# acdr.net
KiCad netlist of a schematic drawn in EAGLE
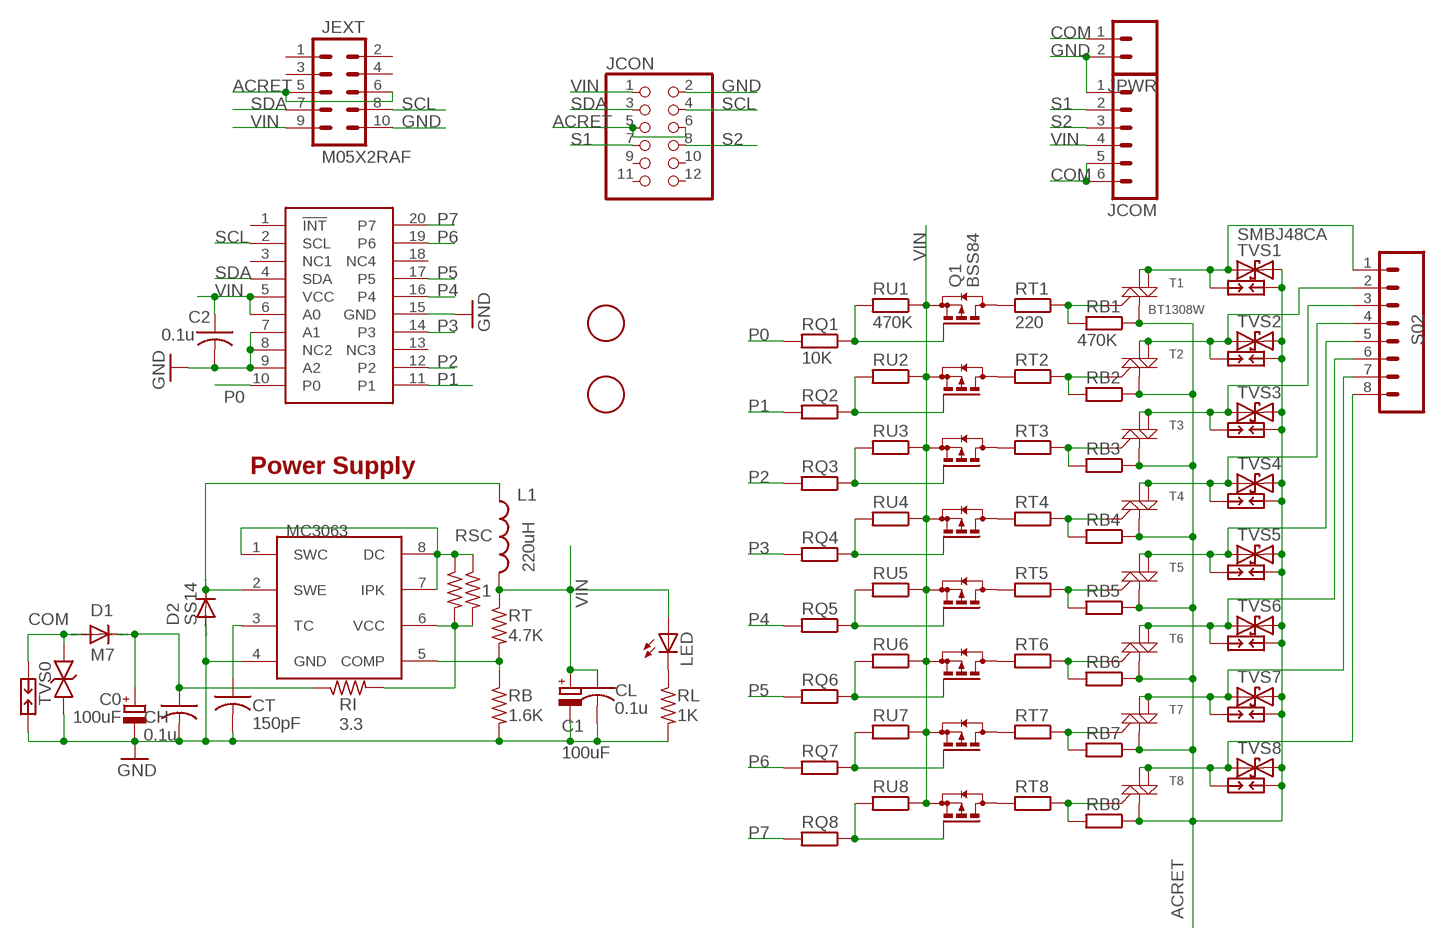
[diagram p0: schematic, sheet 1]

(export (version "E")
  (design (tool "Eeschema 10.0.6"))
  (components
    (comp (ref "C0")
      (value "100uF")
      (footprint "eagle-import:PANASONIC_E")
      (libsource (lib "eagle-import") (part "CPOL-EUE"))
    )
    (comp (ref "C1")
      (value "100uF")
      (footprint "eagle-import:PANASONIC_D")
      (libsource (lib "eagle-import") (part "CPOL-EUD"))
    )
    (comp (ref "C2")
      (value "0.1u")
      (footprint "eagle-import:C0603")
      (libsource (lib "eagle-import") (part "C-USC0603"))
    )
    (comp (ref "CH")
      (value "0.1u")
      (footprint "eagle-import:C0603")
      (libsource (lib "eagle-import") (part "C-USC0603"))
    )
    (comp (ref "CL")
      (value "0.1u")
      (footprint "eagle-import:C0603")
      (libsource (lib "eagle-import") (part "C-USC0603"))
    )
    (comp (ref "CT")
      (value "150pF")
      (footprint "eagle-import:C0603K")
      (libsource (lib "eagle-import") (part "C-USC0603K"))
    )
    (comp (ref "D1")
      (value "M7")
      (footprint "eagle-import:DO-214AC")
      (libsource (lib "eagle-import") (part "DIODE-DO-214AC"))
    )
    (comp (ref "D2")
      (value "SS14")
      (footprint "eagle-import:DO-214AC")
      (libsource (lib "eagle-import") (part "DIODE-DO-214AC"))
    )
    (comp (ref "JCOM")
      (value "M065MM")
      (footprint "eagle-import:SCREWTERMINAL-5MM-6")
      (libsource (lib "eagle-import") (part "M065MM"))
    )
    (comp (ref "JCON")
      (value "PINHD-2X6")
      (footprint "eagle-import:2X06")
      (libsource (lib "eagle-import") (part "PINHD-2X6"))
    )
    (comp (ref "JEXT")
      (value "M05X2RAF")
      (footprint "eagle-import:2X5-RAF")
      (libsource (lib "eagle-import") (part "M05X2RAF"))
    )
    (comp (ref "JPWR")
      (value "M024MM-X")
      (footprint "eagle-import:SCREWTERMINAL-4MM-2-X")
      (libsource (lib "eagle-import") (part "M024MM-X"))
    )
    (comp (ref "L1")
      (value "220uH")
      (footprint "eagle-import:SRU1038")
      (libsource (lib "eagle-import") (part "INDUCTORSRU1038"))
    )
    (comp (ref "LED")
      (value "LEDCHIPLED_0805")
      (footprint "eagle-import:CHIPLED_0805")
      (libsource (lib "eagle-import") (part "LEDCHIPLED_0805"))
    )
    (comp (ref "MC3063")
      (value "34063")
      (footprint "eagle-import:SO08")
      (libsource (lib "eagle-import") (part "MC33063/MC34063D"))
    )
    (comp (ref "PCF8574")
      (value "PCF8574")
      (footprint "eagle-import:SSOP20")
      (libsource (lib "eagle-import") (part "PCF8574"))
    )
    (comp (ref "Q1")
      (value "BSS84")
      (footprint "eagle-import:SOT23")
      (libsource (lib "eagle-import") (part "BSS84"))
    )
    (comp (ref "Q2")
      (value "BSS84")
      (footprint "eagle-import:SOT23")
      (libsource (lib "eagle-import") (part "BSS84"))
    )
    (comp (ref "Q3")
      (value "BSS84")
      (footprint "eagle-import:SOT23")
      (libsource (lib "eagle-import") (part "BSS84"))
    )
    (comp (ref "Q4")
      (value "BSS84")
      (footprint "eagle-import:SOT23")
      (libsource (lib "eagle-import") (part "BSS84"))
    )
    (comp (ref "Q5")
      (value "BSS84")
      (footprint "eagle-import:SOT23")
      (libsource (lib "eagle-import") (part "BSS84"))
    )
    (comp (ref "Q6")
      (value "BSS84")
      (footprint "eagle-import:SOT23")
      (libsource (lib "eagle-import") (part "BSS84"))
    )
    (comp (ref "Q7")
      (value "BSS84")
      (footprint "eagle-import:SOT23")
      (libsource (lib "eagle-import") (part "BSS84"))
    )
    (comp (ref "Q8")
      (value "BSS84")
      (footprint "eagle-import:SOT23")
      (libsource (lib "eagle-import") (part "BSS84"))
    )
    (comp (ref "RB")
      (value "1.6K")
      (footprint "eagle-import:R0603")
      (libsource (lib "eagle-import") (part "adafruitGood_R-US_R0603"))
    )
    (comp (ref "RB1")
      (value "470K")
      (footprint "eagle-import:R0603")
      (libsource (lib "eagle-import") (part "R-EU_R0603"))
    )
    (comp (ref "RB2")
      (value "470K")
      (footprint "eagle-import:R0603")
      (libsource (lib "eagle-import") (part "R-EU_R0603"))
    )
    (comp (ref "RB3")
      (value "470K")
      (footprint "eagle-import:R0603")
      (libsource (lib "eagle-import") (part "R-EU_R0603"))
    )
    (comp (ref "RB4")
      (value "470K")
      (footprint "eagle-import:R0603")
      (libsource (lib "eagle-import") (part "R-EU_R0603"))
    )
    (comp (ref "RB5")
      (value "470K")
      (footprint "eagle-import:R0603")
      (libsource (lib "eagle-import") (part "R-EU_R0603"))
    )
    (comp (ref "RB6")
      (value "470K")
      (footprint "eagle-import:R0603")
      (libsource (lib "eagle-import") (part "R-EU_R0603"))
    )
    (comp (ref "RB7")
      (value "470K")
      (footprint "eagle-import:R0603")
      (libsource (lib "eagle-import") (part "R-EU_R0603"))
    )
    (comp (ref "RB8")
      (value "470K")
      (footprint "eagle-import:R0603")
      (libsource (lib "eagle-import") (part "R-EU_R0603"))
    )
    (comp (ref "RI")
      (value "3.3")
      (footprint "eagle-import:R2010")
      (libsource (lib "eagle-import") (part "adafruitGood_R-US_R2010"))
    )
    (comp (ref "RL")
      (value "1K")
      (footprint "eagle-import:R0603")
      (libsource (lib "eagle-import") (part "R-US_R0603"))
    )
    (comp (ref "RQ1")
      (value "10K")
      (footprint "eagle-import:R0603")
      (libsource (lib "eagle-import") (part "R-EU_R0603"))
    )
    (comp (ref "RQ2")
      (value "10K")
      (footprint "eagle-import:R0603")
      (libsource (lib "eagle-import") (part "R-EU_R0603"))
    )
    (comp (ref "RQ3")
      (value "10K")
      (footprint "eagle-import:R0603")
      (libsource (lib "eagle-import") (part "R-EU_R0603"))
    )
    (comp (ref "RQ4")
      (value "10K")
      (footprint "eagle-import:R0603")
      (libsource (lib "eagle-import") (part "R-EU_R0603"))
    )
    (comp (ref "RQ5")
      (value "10K")
      (footprint "eagle-import:R0603")
      (libsource (lib "eagle-import") (part "R-EU_R0603"))
    )
    (comp (ref "RQ6")
      (value "10K")
      (footprint "eagle-import:R0603")
      (libsource (lib "eagle-import") (part "R-EU_R0603"))
    )
    (comp (ref "RQ7")
      (value "10K")
      (footprint "eagle-import:R0603")
      (libsource (lib "eagle-import") (part "R-EU_R0603"))
    )
    (comp (ref "RQ8")
      (value "10K")
      (footprint "eagle-import:R0603")
      (libsource (lib "eagle-import") (part "R-EU_R0603"))
    )
    (comp (ref "RSC")
      (value "1")
      (footprint "eagle-import:R0805")
      (libsource (lib "eagle-import") (part "adafruitGood_R-US_R0805"))
    )
    (comp (ref "RSC1")
      (value "1")
      (footprint "eagle-import:R0805")
      (libsource (lib "eagle-import") (part "adafruitGood_R-US_R0805"))
    )
    (comp (ref "RT")
      (value "4.7K")
      (footprint "eagle-import:R0805")
      (libsource (lib "eagle-import") (part "adafruitGood_R-US_R0805"))
    )
    (comp (ref "RT1")
      (value "220")
      (footprint "eagle-import:R0603")
      (libsource (lib "eagle-import") (part "R-EU_R0603"))
    )
    (comp (ref "RT2")
      (value "220")
      (footprint "eagle-import:R0603")
      (libsource (lib "eagle-import") (part "R-EU_R0603"))
    )
    (comp (ref "RT3")
      (value "220")
      (footprint "eagle-import:R0603")
      (libsource (lib "eagle-import") (part "R-EU_R0603"))
    )
    (comp (ref "RT4")
      (value "220")
      (footprint "eagle-import:R0603")
      (libsource (lib "eagle-import") (part "R-EU_R0603"))
    )
    (comp (ref "RT5")
      (value "220")
      (footprint "eagle-import:R0603")
      (libsource (lib "eagle-import") (part "R-EU_R0603"))
    )
    (comp (ref "RT6")
      (value "220")
      (footprint "eagle-import:R0603")
      (libsource (lib "eagle-import") (part "R-EU_R0603"))
    )
    (comp (ref "RT7")
      (value "220")
      (footprint "eagle-import:R0603")
      (libsource (lib "eagle-import") (part "R-EU_R0603"))
    )
    (comp (ref "RT8")
      (value "220")
      (footprint "eagle-import:R0603")
      (libsource (lib "eagle-import") (part "R-EU_R0603"))
    )
    (comp (ref "RU1")
      (value "470K")
      (footprint "eagle-import:R0603")
      (libsource (lib "eagle-import") (part "R-EU_R0603"))
    )
    (comp (ref "RU2")
      (value "470K")
      (footprint "eagle-import:R0603")
      (libsource (lib "eagle-import") (part "R-EU_R0603"))
    )
    (comp (ref "RU3")
      (value "470K")
      (footprint "eagle-import:R0603")
      (libsource (lib "eagle-import") (part "R-EU_R0603"))
    )
    (comp (ref "RU4")
      (value "470K")
      (footprint "eagle-import:R0603")
      (libsource (lib "eagle-import") (part "R-EU_R0603"))
    )
    (comp (ref "RU5")
      (value "470K")
      (footprint "eagle-import:R0603")
      (libsource (lib "eagle-import") (part "R-EU_R0603"))
    )
    (comp (ref "RU6")
      (value "470K")
      (footprint "eagle-import:R0603")
      (libsource (lib "eagle-import") (part "R-EU_R0603"))
    )
    (comp (ref "RU7")
      (value "470K")
      (footprint "eagle-import:R0603")
      (libsource (lib "eagle-import") (part "R-EU_R0603"))
    )
    (comp (ref "RU8")
      (value "470K")
      (footprint "eagle-import:R0603")
      (libsource (lib "eagle-import") (part "R-EU_R0603"))
    )
    (comp (ref "S02")
      (value "M085MM-8")
      (footprint "eagle-import:SCREWTERMINAL-5MM-8")
      (libsource (lib "eagle-import") (part "M085MM-8"))
    )
    (comp (ref "SP0")
      (value "PCB-SGAP")
      (footprint "eagle-import:PCB-SGAP")
      (libsource (lib "eagle-import") (part "PCB-SGAP"))
    )
    (comp (ref "SP1")
      (value "PCB-SGAP")
      (footprint "eagle-import:PCB-SGAP")
      (libsource (lib "eagle-import") (part "PCB-SGAP"))
    )
    (comp (ref "SP2")
      (value "PCB-SGAP")
      (footprint "eagle-import:PCB-SGAP")
      (libsource (lib "eagle-import") (part "PCB-SGAP"))
    )
    (comp (ref "SP3")
      (value "PCB-SGAP")
      (footprint "eagle-import:PCB-SGAP")
      (libsource (lib "eagle-import") (part "PCB-SGAP"))
    )
    (comp (ref "SP4")
      (value "PCB-SGAP")
      (footprint "eagle-import:PCB-SGAP")
      (libsource (lib "eagle-import") (part "PCB-SGAP"))
    )
    (comp (ref "SP5")
      (value "PCB-SGAP")
      (footprint "eagle-import:PCB-SGAP")
      (libsource (lib "eagle-import") (part "PCB-SGAP"))
    )
    (comp (ref "SP6")
      (value "PCB-SGAP")
      (footprint "eagle-import:PCB-SGAP")
      (libsource (lib "eagle-import") (part "PCB-SGAP"))
    )
    (comp (ref "SP7")
      (value "PCB-SGAP")
      (footprint "eagle-import:PCB-SGAP")
      (libsource (lib "eagle-import") (part "PCB-SGAP"))
    )
    (comp (ref "SP8")
      (value "PCB-SGAP")
      (footprint "eagle-import:PCB-SGAP")
      (libsource (lib "eagle-import") (part "PCB-SGAP"))
    )
    (comp (ref "T1")
      (value "BT1308W")
      (footprint "eagle-import:SOT223")
      (libsource (lib "eagle-import") (part "MAC97SOT223"))
    )
    (comp (ref "T2")
      (value "MAC97SOT223")
      (footprint "eagle-import:SOT223")
      (libsource (lib "eagle-import") (part "MAC97SOT223"))
    )
    (comp (ref "T3")
      (value "MAC97SOT223")
      (footprint "eagle-import:SOT223")
      (libsource (lib "eagle-import") (part "MAC97SOT223"))
    )
    (comp (ref "T4")
      (value "MAC97SOT223")
      (footprint "eagle-import:SOT223")
      (libsource (lib "eagle-import") (part "MAC97SOT223"))
    )
    (comp (ref "T5")
      (value "MAC97SOT223")
      (footprint "eagle-import:SOT223")
      (libsource (lib "eagle-import") (part "MAC97SOT223"))
    )
    (comp (ref "T6")
      (value "MAC97SOT223")
      (footprint "eagle-import:SOT223")
      (libsource (lib "eagle-import") (part "MAC97SOT223"))
    )
    (comp (ref "T7")
      (value "MAC97SOT223")
      (footprint "eagle-import:SOT223")
      (libsource (lib "eagle-import") (part "MAC97SOT223"))
    )
    (comp (ref "T8")
      (value "MAC97SOT223")
      (footprint "eagle-import:SOT223")
      (libsource (lib "eagle-import") (part "MAC97SOT223"))
    )
    (comp (ref "TVS0")
      (value "43CA")
      (footprint "eagle-import:SMB")
      (libsource (lib "eagle-import") (part "DIODE-BTVSSMB"))
    )
    (comp (ref "TVS1")
      (value "SMBJ48CA")
      (footprint "eagle-import:SMB")
      (libsource (lib "eagle-import") (part "TVSSMB"))
    )
    (comp (ref "TVS2")
      (value "TVSSMB")
      (footprint "eagle-import:SMB")
      (libsource (lib "eagle-import") (part "TVSSMB"))
    )
    (comp (ref "TVS3")
      (value "TVSSMB")
      (footprint "eagle-import:SMB")
      (libsource (lib "eagle-import") (part "TVSSMB"))
    )
    (comp (ref "TVS4")
      (value "TVSSMB")
      (footprint "eagle-import:SMB")
      (libsource (lib "eagle-import") (part "TVSSMB"))
    )
    (comp (ref "TVS5")
      (value "TVSSMB")
      (footprint "eagle-import:SMB")
      (libsource (lib "eagle-import") (part "TVSSMB"))
    )
    (comp (ref "TVS6")
      (value "TVSSMB")
      (footprint "eagle-import:SMB")
      (libsource (lib "eagle-import") (part "TVSSMB"))
    )
    (comp (ref "TVS7")
      (value "TVSSMB")
      (footprint "eagle-import:SMB")
      (libsource (lib "eagle-import") (part "TVSSMB"))
    )
    (comp (ref "TVS8")
      (value "TVSSMB")
      (footprint "eagle-import:SMB")
      (libsource (lib "eagle-import") (part "TVSSMB"))
    )
    (comp (ref "U$1")
      (value "FIDUCIAL")
      (footprint "eagle-import:FIDUCIAL_1MM")
      (libsource (lib "eagle-import") (part "FIDUCIAL"))
    )
    (comp (ref "U$2")
      (value "FIDUCIAL")
      (footprint "eagle-import:FIDUCIAL_1MM")
      (libsource (lib "eagle-import") (part "FIDUCIAL"))
    )
  )
  (nets
    (net (code "1") (name "/ACRET") (class "Default")
      (node (ref "JCON") (pin "5") (pinfunction "5_5") (pintype "passive"))
      (node (ref "JCON") (pin "6") (pinfunction "6_6") (pintype "passive"))
      (node (ref "JEXT") (pin "5") (pinfunction "5_5") (pintype "passive"))
      (node (ref "JEXT") (pin "6") (pinfunction "6_6") (pintype "passive"))
      (node (ref "RB1") (pin "1") (pinfunction "1_1") (pintype "passive"))
      (node (ref "RB2") (pin "1") (pinfunction "1_1") (pintype "passive"))
      (node (ref "RB3") (pin "1") (pinfunction "1_1") (pintype "passive"))
      (node (ref "RB4") (pin "1") (pinfunction "1_1") (pintype "passive"))
      (node (ref "RB5") (pin "1") (pinfunction "1_1") (pintype "passive"))
      (node (ref "RB6") (pin "1") (pinfunction "1_1") (pintype "passive"))
      (node (ref "RB7") (pin "1") (pinfunction "1_1") (pintype "passive"))
      (node (ref "RB8") (pin "1") (pinfunction "1_1") (pintype "passive"))
      (node (ref "SP1") (pin "1") (pinfunction "1_1") (pintype "passive"))
      (node (ref "SP2") (pin "1") (pinfunction "1_1") (pintype "passive"))
      (node (ref "SP3") (pin "1") (pinfunction "1_1") (pintype "passive"))
      (node (ref "SP4") (pin "1") (pinfunction "1_1") (pintype "passive"))
      (node (ref "SP5") (pin "1") (pinfunction "1_1") (pintype "passive"))
      (node (ref "SP6") (pin "1") (pinfunction "1_1") (pintype "passive"))
      (node (ref "SP7") (pin "1") (pinfunction "1_1") (pintype "passive"))
      (node (ref "SP8") (pin "1") (pinfunction "1_1") (pintype "passive"))
      (node (ref "T1") (pin "1") (pinfunction "M1_1") (pintype "bidirectional"))
      (node (ref "T2") (pin "1") (pinfunction "M1_1") (pintype "bidirectional"))
      (node (ref "T3") (pin "1") (pinfunction "M1_1") (pintype "bidirectional"))
      (node (ref "T4") (pin "1") (pinfunction "M1_1") (pintype "bidirectional"))
      (node (ref "T5") (pin "1") (pinfunction "M1_1") (pintype "bidirectional"))
      (node (ref "T6") (pin "1") (pinfunction "M1_1") (pintype "bidirectional"))
      (node (ref "T7") (pin "1") (pinfunction "M1_1") (pintype "bidirectional"))
      (node (ref "T8") (pin "1") (pinfunction "M1_1") (pintype "bidirectional"))
      (node (ref "TVS1") (pin "C") (pinfunction "C_C") (pintype "passive"))
      (node (ref "TVS2") (pin "C") (pinfunction "C_C") (pintype "passive"))
      (node (ref "TVS3") (pin "C") (pinfunction "C_C") (pintype "passive"))
      (node (ref "TVS4") (pin "C") (pinfunction "C_C") (pintype "passive"))
      (node (ref "TVS5") (pin "C") (pinfunction "C_C") (pintype "passive"))
      (node (ref "TVS6") (pin "C") (pinfunction "C_C") (pintype "passive"))
      (node (ref "TVS7") (pin "C") (pinfunction "C_C") (pintype "passive"))
      (node (ref "TVS8") (pin "C") (pinfunction "C_C") (pintype "passive"))
    )
    (net (code "2") (name "/COM") (class "Default")
      (node (ref "D1") (pin "A") (pinfunction "A_A") (pintype "passive"))
      (node (ref "JCOM") (pin "5") (pinfunction "5_5") (pintype "passive"))
      (node (ref "JCOM") (pin "6") (pinfunction "6_6") (pintype "passive"))
      (node (ref "JPWR") (pin "1") (pinfunction "1_1") (pintype "passive"))
      (node (ref "SP0") (pin "1") (pinfunction "1_1") (pintype "passive"))
      (node (ref "TVS0") (pin "C") (pinfunction "C_C") (pintype "passive"))
    )
    (net (code "3") (name "/P0") (class "Default")
      (node (ref "PCF8574") (pin "10") (pinfunction "P0_10") (pintype "bidirectional"))
      (node (ref "RQ1") (pin "2") (pinfunction "2_2") (pintype "passive"))
    )
    (net (code "4") (name "/P1") (class "Default")
      (node (ref "PCF8574") (pin "11") (pinfunction "P1_11") (pintype "bidirectional"))
      (node (ref "RQ2") (pin "2") (pinfunction "2_2") (pintype "passive"))
    )
    (net (code "5") (name "/P2") (class "Default")
      (node (ref "PCF8574") (pin "12") (pinfunction "P2_12") (pintype "bidirectional"))
      (node (ref "RQ3") (pin "2") (pinfunction "2_2") (pintype "passive"))
    )
    (net (code "6") (name "/P3") (class "Default")
      (node (ref "PCF8574") (pin "14") (pinfunction "P3_14") (pintype "bidirectional"))
      (node (ref "RQ4") (pin "2") (pinfunction "2_2") (pintype "passive"))
    )
    (net (code "7") (name "/P4") (class "Default")
      (node (ref "PCF8574") (pin "16") (pinfunction "P4_16") (pintype "bidirectional"))
      (node (ref "RQ5") (pin "2") (pinfunction "2_2") (pintype "passive"))
    )
    (net (code "8") (name "/P5") (class "Default")
      (node (ref "PCF8574") (pin "17") (pinfunction "P5_17") (pintype "bidirectional"))
      (node (ref "RQ6") (pin "2") (pinfunction "2_2") (pintype "passive"))
    )
    (net (code "9") (name "/P6") (class "Default")
      (node (ref "PCF8574") (pin "19") (pinfunction "P6_19") (pintype "bidirectional"))
      (node (ref "RQ7") (pin "2") (pinfunction "2_2") (pintype "passive"))
    )
    (net (code "10") (name "/P7") (class "Default")
      (node (ref "PCF8574") (pin "20") (pinfunction "P7_20") (pintype "bidirectional"))
      (node (ref "RQ8") (pin "2") (pinfunction "2_2") (pintype "passive"))
    )
    (net (code "11") (name "/S1") (class "Default")
      (node (ref "JCOM") (pin "2") (pinfunction "2_2") (pintype "passive"))
      (node (ref "JCON") (pin "7") (pinfunction "7_7") (pintype "passive"))
    )
    (net (code "12") (name "/S2") (class "Default")
      (node (ref "JCOM") (pin "3") (pinfunction "3_3") (pintype "passive"))
      (node (ref "JCON") (pin "8") (pinfunction "8_8") (pintype "passive"))
    )
    (net (code "13") (name "/SCL") (class "Default")
      (node (ref "JCON") (pin "4") (pinfunction "4_4") (pintype "passive"))
      (node (ref "JEXT") (pin "8") (pinfunction "8_8") (pintype "passive"))
      (node (ref "PCF8574") (pin "2") (pinfunction "SCL_2") (pintype "bidirectional"))
    )
    (net (code "14") (name "/SDA") (class "Default")
      (node (ref "JCON") (pin "3") (pinfunction "3_3") (pintype "passive"))
      (node (ref "JEXT") (pin "7") (pinfunction "7_7") (pintype "passive"))
      (node (ref "PCF8574") (pin "4") (pinfunction "SDA_4") (pintype "bidirectional"))
    )
    (net (code "15") (name "/VIN") (class "Default")
      (node (ref "C1") (pin "+") (pinfunction "+_+") (pintype "passive"))
      (node (ref "C2") (pin "1") (pinfunction "1_1") (pintype "passive"))
      (node (ref "CL") (pin "1") (pinfunction "1_1") (pintype "passive"))
      (node (ref "JCOM") (pin "4") (pinfunction "4_4") (pintype "passive"))
      (node (ref "JCON") (pin "1") (pinfunction "1_1") (pintype "passive"))
      (node (ref "JEXT") (pin "9") (pinfunction "9_9") (pintype "passive"))
      (node (ref "L1") (pin "2") (pinfunction "2_2") (pintype "passive"))
      (node (ref "LED") (pin "A") (pinfunction "A_A") (pintype "passive"))
      (node (ref "PCF8574") (pin "5") (pinfunction "VCC_5") (pintype "power_in"))
      (node (ref "PCF8574") (pin "6") (pinfunction "A0_6") (pintype "bidirectional"))
      (node (ref "Q1") (pin "2") (pinfunction "S_2") (pintype "passive"))
      (node (ref "Q2") (pin "2") (pinfunction "S_2") (pintype "passive"))
      (node (ref "Q3") (pin "2") (pinfunction "S_2") (pintype "passive"))
      (node (ref "Q4") (pin "2") (pinfunction "S_2") (pintype "passive"))
      (node (ref "Q5") (pin "2") (pinfunction "S_2") (pintype "passive"))
      (node (ref "Q6") (pin "2") (pinfunction "S_2") (pintype "passive"))
      (node (ref "Q7") (pin "2") (pinfunction "S_2") (pintype "passive"))
      (node (ref "Q8") (pin "2") (pinfunction "S_2") (pintype "passive"))
      (node (ref "RT") (pin "1") (pinfunction "1_1") (pintype "passive"))
      (node (ref "RU1") (pin "1") (pinfunction "1_1") (pintype "passive"))
      (node (ref "RU2") (pin "1") (pinfunction "1_1") (pintype "passive"))
      (node (ref "RU3") (pin "1") (pinfunction "1_1") (pintype "passive"))
      (node (ref "RU4") (pin "1") (pinfunction "1_1") (pintype "passive"))
      (node (ref "RU5") (pin "1") (pinfunction "1_1") (pintype "passive"))
      (node (ref "RU6") (pin "1") (pinfunction "1_1") (pintype "passive"))
      (node (ref "RU7") (pin "1") (pinfunction "1_1") (pintype "passive"))
      (node (ref "RU8") (pin "1") (pinfunction "1_1") (pintype "passive"))
    )
    (net (code "16") (name "GND") (class "Default")
      (node (ref "C0") (pin "-") (pinfunction "-_-") (pintype "passive"))
      (node (ref "C1") (pin "-") (pinfunction "-_-") (pintype "passive"))
      (node (ref "C2") (pin "2") (pinfunction "2_2") (pintype "passive"))
      (node (ref "CH") (pin "2") (pinfunction "2_2") (pintype "passive"))
      (node (ref "CL") (pin "2") (pinfunction "2_2") (pintype "passive"))
      (node (ref "CT") (pin "2") (pinfunction "2_2") (pintype "passive"))
      (node (ref "D2") (pin "A") (pinfunction "A_A") (pintype "passive"))
      (node (ref "JCOM") (pin "1") (pinfunction "1_1") (pintype "passive"))
      (node (ref "JCON") (pin "2") (pinfunction "2_2") (pintype "passive"))
      (node (ref "JEXT") (pin "10") (pinfunction "10_10") (pintype "passive"))
      (node (ref "JPWR") (pin "2") (pinfunction "2_2") (pintype "passive"))
      (node (ref "MC3063") (pin "4") (pinfunction "GND_4") (pintype "power_in"))
      (node (ref "PCF8574") (pin "15") (pinfunction "GND_15") (pintype "power_in"))
      (node (ref "PCF8574") (pin "7") (pinfunction "A1_7") (pintype "bidirectional"))
      (node (ref "PCF8574") (pin "8") (pinfunction "NC2_8") (pintype "bidirectional"))
      (node (ref "PCF8574") (pin "9") (pinfunction "A2_9") (pintype "bidirectional"))
      (node (ref "RB") (pin "2") (pinfunction "2_2") (pintype "passive"))
      (node (ref "RL") (pin "2") (pinfunction "2_2") (pintype "passive"))
      (node (ref "SP0") (pin "2") (pinfunction "2_2") (pintype "passive"))
      (node (ref "TVS0") (pin "A") (pinfunction "A_A") (pintype "passive"))
    )
    (net (code "17") (name "Net-(C0-Pad+)") (class "Default")
      (node (ref "C0") (pin "+") (pinfunction "+_+") (pintype "passive"))
      (node (ref "CH") (pin "1") (pinfunction "1_1") (pintype "passive"))
      (node (ref "D1") (pin "C") (pinfunction "C_C") (pintype "passive"))
      (node (ref "RI") (pin "1") (pinfunction "1_1") (pintype "passive"))
    )
    (net (code "18") (name "Net-(LED-PadC)") (class "Default")
      (node (ref "LED") (pin "C") (pinfunction "C_C") (pintype "passive"))
      (node (ref "RL") (pin "1") (pinfunction "1_1") (pintype "passive"))
    )
    (net (code "19") (name "Net-(MC3063-COMP)") (class "Default")
      (node (ref "MC3063") (pin "5") (pinfunction "COMP_5") (pintype "input"))
      (node (ref "RB") (pin "1") (pinfunction "1_1") (pintype "passive"))
      (node (ref "RT") (pin "2") (pinfunction "2_2") (pintype "passive"))
    )
    (net (code "20") (name "Net-(MC3063-DC)") (class "Default")
      (node (ref "MC3063") (pin "1") (pinfunction "SWC_1") (pintype "input"))
      (node (ref "MC3063") (pin "7") (pinfunction "IPK_7") (pintype "bidirectional"))
      (node (ref "MC3063") (pin "8") (pinfunction "DC_8") (pintype "input"))
      (node (ref "RSC") (pin "1") (pinfunction "1_1") (pintype "passive"))
      (node (ref "RSC1") (pin "1") (pinfunction "1_1") (pintype "passive"))
    )
    (net (code "21") (name "Net-(MC3063-SWE)") (class "Default")
      (node (ref "D2") (pin "C") (pinfunction "C_C") (pintype "passive"))
      (node (ref "L1") (pin "1") (pinfunction "1_1") (pintype "passive"))
      (node (ref "MC3063") (pin "2") (pinfunction "SWE_2") (pintype "input"))
    )
    (net (code "22") (name "Net-(MC3063-TC)") (class "Default")
      (node (ref "CT") (pin "1") (pinfunction "1_1") (pintype "passive"))
      (node (ref "MC3063") (pin "3") (pinfunction "TC_3") (pintype "input"))
    )
    (net (code "23") (name "Net-(MC3063-VCC)") (class "Default")
      (node (ref "MC3063") (pin "6") (pinfunction "VCC_6") (pintype "power_in"))
      (node (ref "RI") (pin "2") (pinfunction "2_2") (pintype "passive"))
      (node (ref "RSC") (pin "2") (pinfunction "2_2") (pintype "passive"))
      (node (ref "RSC1") (pin "2") (pinfunction "2_2") (pintype "passive"))
    )
    (net (code "24") (name "Net-(Q1-D)") (class "Default")
      (node (ref "Q1") (pin "3") (pinfunction "D_3") (pintype "passive"))
      (node (ref "RT1") (pin "2") (pinfunction "2_2") (pintype "passive"))
    )
    (net (code "25") (name "Net-(Q1-G)") (class "Default")
      (node (ref "Q1") (pin "1") (pinfunction "G_1") (pintype "passive"))
      (node (ref "RQ1") (pin "1") (pinfunction "1_1") (pintype "passive"))
      (node (ref "RU1") (pin "2") (pinfunction "2_2") (pintype "passive"))
    )
    (net (code "26") (name "Net-(Q2-D)") (class "Default")
      (node (ref "Q2") (pin "3") (pinfunction "D_3") (pintype "passive"))
      (node (ref "RT2") (pin "2") (pinfunction "2_2") (pintype "passive"))
    )
    (net (code "27") (name "Net-(Q2-G)") (class "Default")
      (node (ref "Q2") (pin "1") (pinfunction "G_1") (pintype "passive"))
      (node (ref "RQ2") (pin "1") (pinfunction "1_1") (pintype "passive"))
      (node (ref "RU2") (pin "2") (pinfunction "2_2") (pintype "passive"))
    )
    (net (code "28") (name "Net-(Q3-D)") (class "Default")
      (node (ref "Q3") (pin "3") (pinfunction "D_3") (pintype "passive"))
      (node (ref "RT3") (pin "2") (pinfunction "2_2") (pintype "passive"))
    )
    (net (code "29") (name "Net-(Q3-G)") (class "Default")
      (node (ref "Q3") (pin "1") (pinfunction "G_1") (pintype "passive"))
      (node (ref "RQ3") (pin "1") (pinfunction "1_1") (pintype "passive"))
      (node (ref "RU3") (pin "2") (pinfunction "2_2") (pintype "passive"))
    )
    (net (code "30") (name "Net-(Q4-D)") (class "Default")
      (node (ref "Q4") (pin "3") (pinfunction "D_3") (pintype "passive"))
      (node (ref "RT4") (pin "2") (pinfunction "2_2") (pintype "passive"))
    )
    (net (code "31") (name "Net-(Q4-G)") (class "Default")
      (node (ref "Q4") (pin "1") (pinfunction "G_1") (pintype "passive"))
      (node (ref "RQ4") (pin "1") (pinfunction "1_1") (pintype "passive"))
      (node (ref "RU4") (pin "2") (pinfunction "2_2") (pintype "passive"))
    )
    (net (code "32") (name "Net-(Q5-D)") (class "Default")
      (node (ref "Q5") (pin "3") (pinfunction "D_3") (pintype "passive"))
      (node (ref "RT5") (pin "2") (pinfunction "2_2") (pintype "passive"))
    )
    (net (code "33") (name "Net-(Q5-G)") (class "Default")
      (node (ref "Q5") (pin "1") (pinfunction "G_1") (pintype "passive"))
      (node (ref "RQ5") (pin "1") (pinfunction "1_1") (pintype "passive"))
      (node (ref "RU5") (pin "2") (pinfunction "2_2") (pintype "passive"))
    )
    (net (code "34") (name "Net-(Q6-D)") (class "Default")
      (node (ref "Q6") (pin "3") (pinfunction "D_3") (pintype "passive"))
      (node (ref "RT6") (pin "2") (pinfunction "2_2") (pintype "passive"))
    )
    (net (code "35") (name "Net-(Q6-G)") (class "Default")
      (node (ref "Q6") (pin "1") (pinfunction "G_1") (pintype "passive"))
      (node (ref "RQ6") (pin "1") (pinfunction "1_1") (pintype "passive"))
      (node (ref "RU6") (pin "2") (pinfunction "2_2") (pintype "passive"))
    )
    (net (code "36") (name "Net-(Q7-D)") (class "Default")
      (node (ref "Q7") (pin "3") (pinfunction "D_3") (pintype "passive"))
      (node (ref "RT7") (pin "2") (pinfunction "2_2") (pintype "passive"))
    )
    (net (code "37") (name "Net-(Q7-G)") (class "Default")
      (node (ref "Q7") (pin "1") (pinfunction "G_1") (pintype "passive"))
      (node (ref "RQ7") (pin "1") (pinfunction "1_1") (pintype "passive"))
      (node (ref "RU7") (pin "2") (pinfunction "2_2") (pintype "passive"))
    )
    (net (code "38") (name "Net-(Q8-D)") (class "Default")
      (node (ref "Q8") (pin "3") (pinfunction "D_3") (pintype "passive"))
      (node (ref "RT8") (pin "2") (pinfunction "2_2") (pintype "passive"))
    )
    (net (code "39") (name "Net-(Q8-G)") (class "Default")
      (node (ref "Q8") (pin "1") (pinfunction "G_1") (pintype "passive"))
      (node (ref "RQ8") (pin "1") (pinfunction "1_1") (pintype "passive"))
      (node (ref "RU8") (pin "2") (pinfunction "2_2") (pintype "passive"))
    )
    (net (code "40") (name "Net-(T1-G)") (class "Default")
      (node (ref "RB1") (pin "2") (pinfunction "2_2") (pintype "passive"))
      (node (ref "RT1") (pin "1") (pinfunction "1_1") (pintype "passive"))
      (node (ref "T1") (pin "3") (pinfunction "G_3") (pintype "bidirectional"))
    )
    (net (code "41") (name "Net-(T1-M2)") (class "Default")
      (node (ref "S02") (pin "1") (pinfunction "1_1") (pintype "passive"))
      (node (ref "SP1") (pin "2") (pinfunction "2_2") (pintype "passive"))
      (node (ref "T1") (pin "2") (pinfunction "M2_2") (pintype "bidirectional"))
      (node (ref "T1") (pin "4") (pinfunction "M2-4_4") (pintype "bidirectional"))
      (node (ref "TVS1") (pin "A") (pinfunction "A_A") (pintype "passive"))
    )
    (net (code "42") (name "Net-(T2-G)") (class "Default")
      (node (ref "RB2") (pin "2") (pinfunction "2_2") (pintype "passive"))
      (node (ref "RT2") (pin "1") (pinfunction "1_1") (pintype "passive"))
      (node (ref "T2") (pin "3") (pinfunction "G_3") (pintype "bidirectional"))
    )
    (net (code "43") (name "Net-(T2-M2)") (class "Default")
      (node (ref "S02") (pin "2") (pinfunction "2_2") (pintype "passive"))
      (node (ref "SP2") (pin "2") (pinfunction "2_2") (pintype "passive"))
      (node (ref "T2") (pin "2") (pinfunction "M2_2") (pintype "bidirectional"))
      (node (ref "T2") (pin "4") (pinfunction "M2-4_4") (pintype "bidirectional"))
      (node (ref "TVS2") (pin "A") (pinfunction "A_A") (pintype "passive"))
    )
    (net (code "44") (name "Net-(T3-G)") (class "Default")
      (node (ref "RB3") (pin "2") (pinfunction "2_2") (pintype "passive"))
      (node (ref "RT3") (pin "1") (pinfunction "1_1") (pintype "passive"))
      (node (ref "T3") (pin "3") (pinfunction "G_3") (pintype "bidirectional"))
    )
    (net (code "45") (name "Net-(T3-M2)") (class "Default")
      (node (ref "S02") (pin "3") (pinfunction "3_3") (pintype "passive"))
      (node (ref "SP3") (pin "2") (pinfunction "2_2") (pintype "passive"))
      (node (ref "T3") (pin "2") (pinfunction "M2_2") (pintype "bidirectional"))
      (node (ref "T3") (pin "4") (pinfunction "M2-4_4") (pintype "bidirectional"))
      (node (ref "TVS3") (pin "A") (pinfunction "A_A") (pintype "passive"))
    )
    (net (code "46") (name "Net-(T4-G)") (class "Default")
      (node (ref "RB4") (pin "2") (pinfunction "2_2") (pintype "passive"))
      (node (ref "RT4") (pin "1") (pinfunction "1_1") (pintype "passive"))
      (node (ref "T4") (pin "3") (pinfunction "G_3") (pintype "bidirectional"))
    )
    (net (code "47") (name "Net-(T4-M2)") (class "Default")
      (node (ref "S02") (pin "4") (pinfunction "4_4") (pintype "passive"))
      (node (ref "SP4") (pin "2") (pinfunction "2_2") (pintype "passive"))
      (node (ref "T4") (pin "2") (pinfunction "M2_2") (pintype "bidirectional"))
      (node (ref "T4") (pin "4") (pinfunction "M2-4_4") (pintype "bidirectional"))
      (node (ref "TVS4") (pin "A") (pinfunction "A_A") (pintype "passive"))
    )
    (net (code "48") (name "Net-(T5-G)") (class "Default")
      (node (ref "RB5") (pin "2") (pinfunction "2_2") (pintype "passive"))
      (node (ref "RT5") (pin "1") (pinfunction "1_1") (pintype "passive"))
      (node (ref "T5") (pin "3") (pinfunction "G_3") (pintype "bidirectional"))
    )
    (net (code "49") (name "Net-(T5-M2)") (class "Default")
      (node (ref "S02") (pin "5") (pinfunction "5_5") (pintype "passive"))
      (node (ref "SP5") (pin "2") (pinfunction "2_2") (pintype "passive"))
      (node (ref "T5") (pin "2") (pinfunction "M2_2") (pintype "bidirectional"))
      (node (ref "T5") (pin "4") (pinfunction "M2-4_4") (pintype "bidirectional"))
      (node (ref "TVS5") (pin "A") (pinfunction "A_A") (pintype "passive"))
    )
    (net (code "50") (name "Net-(T6-G)") (class "Default")
      (node (ref "RB6") (pin "2") (pinfunction "2_2") (pintype "passive"))
      (node (ref "RT6") (pin "1") (pinfunction "1_1") (pintype "passive"))
      (node (ref "T6") (pin "3") (pinfunction "G_3") (pintype "bidirectional"))
    )
    (net (code "51") (name "Net-(T6-M2)") (class "Default")
      (node (ref "S02") (pin "6") (pinfunction "6_6") (pintype "passive"))
      (node (ref "SP6") (pin "2") (pinfunction "2_2") (pintype "passive"))
      (node (ref "T6") (pin "2") (pinfunction "M2_2") (pintype "bidirectional"))
      (node (ref "T6") (pin "4") (pinfunction "M2-4_4") (pintype "bidirectional"))
      (node (ref "TVS6") (pin "A") (pinfunction "A_A") (pintype "passive"))
    )
    (net (code "52") (name "Net-(T7-G)") (class "Default")
      (node (ref "RB7") (pin "2") (pinfunction "2_2") (pintype "passive"))
      (node (ref "RT7") (pin "1") (pinfunction "1_1") (pintype "passive"))
      (node (ref "T7") (pin "3") (pinfunction "G_3") (pintype "bidirectional"))
    )
    (net (code "53") (name "Net-(T7-M2)") (class "Default")
      (node (ref "S02") (pin "7") (pinfunction "7_7") (pintype "passive"))
      (node (ref "SP7") (pin "2") (pinfunction "2_2") (pintype "passive"))
      (node (ref "T7") (pin "2") (pinfunction "M2_2") (pintype "bidirectional"))
      (node (ref "T7") (pin "4") (pinfunction "M2-4_4") (pintype "bidirectional"))
      (node (ref "TVS7") (pin "A") (pinfunction "A_A") (pintype "passive"))
    )
    (net (code "54") (name "Net-(T8-G)") (class "Default")
      (node (ref "RB8") (pin "2") (pinfunction "2_2") (pintype "passive"))
      (node (ref "RT8") (pin "1") (pinfunction "1_1") (pintype "passive"))
      (node (ref "T8") (pin "3") (pinfunction "G_3") (pintype "bidirectional"))
    )
    (net (code "55") (name "Net-(T8-M2)") (class "Default")
      (node (ref "S02") (pin "8") (pinfunction "8_8") (pintype "passive"))
      (node (ref "SP8") (pin "2") (pinfunction "2_2") (pintype "passive"))
      (node (ref "T8") (pin "2") (pinfunction "M2_2") (pintype "bidirectional"))
      (node (ref "T8") (pin "4") (pinfunction "M2-4_4") (pintype "bidirectional"))
      (node (ref "TVS8") (pin "A") (pinfunction "A_A") (pintype "passive"))
    )
    (net (code "56") (name "unconnected-(JCON-Pad9)") (class "Default")
      (node (ref "JCON") (pin "9") (pinfunction "9_9") (pintype "passive"))
    )
    (net (code "57") (name "unconnected-(JCON-Pad10)") (class "Default")
      (node (ref "JCON") (pin "10") (pinfunction "10_10") (pintype "passive"))
    )
    (net (code "58") (name "unconnected-(JCON-Pad11)") (class "Default")
      (node (ref "JCON") (pin "11") (pinfunction "11_11") (pintype "passive"))
    )
    (net (code "59") (name "unconnected-(JCON-Pad12)") (class "Default")
      (node (ref "JCON") (pin "12") (pinfunction "12_12") (pintype "passive"))
    )
    (net (code "60") (name "unconnected-(JEXT-Pad1)") (class "Default")
      (node (ref "JEXT") (pin "1") (pinfunction "1_1") (pintype "passive"))
    )
    (net (code "61") (name "unconnected-(JEXT-Pad2)") (class "Default")
      (node (ref "JEXT") (pin "2") (pinfunction "2_2") (pintype "passive"))
    )
    (net (code "62") (name "unconnected-(JEXT-Pad3)") (class "Default")
      (node (ref "JEXT") (pin "3") (pinfunction "3_3") (pintype "passive"))
    )
    (net (code "63") (name "unconnected-(JEXT-Pad4)") (class "Default")
      (node (ref "JEXT") (pin "4") (pinfunction "4_4") (pintype "passive"))
    )
    (net (code "64") (name "unconnected-(PCF8574-NC1-Pad3)") (class "Default")
      (node (ref "PCF8574") (pin "3") (pinfunction "NC1_3") (pintype "bidirectional"))
    )
    (net (code "65") (name "unconnected-(PCF8574-NC3-Pad13)") (class "Default")
      (node (ref "PCF8574") (pin "13") (pinfunction "NC3_13") (pintype "bidirectional"))
    )
    (net (code "66") (name "unconnected-(PCF8574-NC4-Pad18)") (class "Default")
      (node (ref "PCF8574") (pin "18") (pinfunction "NC4_18") (pintype "bidirectional"))
    )
    (net (code "67") (name "unconnected-(PCF8574-~{INT}-Pad1)") (class "Default")
      (node (ref "PCF8574") (pin "1") (pinfunction "~{INT}_1") (pintype "bidirectional"))
    )
  )
)
